# HeatedBed.net
KiCad netlist of a schematic drawn in Altium Designer
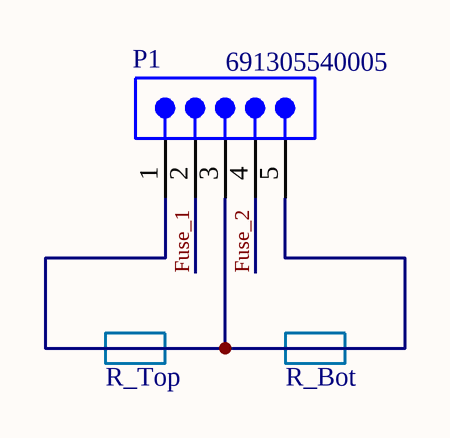
[diagram p0: HeatedBed.SchDoc]

(export (version "E")
  (design (tool "Eeschema 10.0.6"))
  (components
    (comp (ref "P1")
      (value "691305540005")
      (footprint "691305540005")
      (description "691305540005 Terminal Block, R/A Header, 5Pos, Th Rohs Compliant: Yes")
      (libsource (lib "Altium Content Vault") (part "TBL - 1R - 05P - Male"))
    )
  )
  (nets
    (net (code "1") (name "/Fuse_1") (class "Default")
      (node (ref "P1") (pin "2") (pinfunction "2_2") (pintype "passive"))
    )
    (net (code "2") (name "/Fuse_2") (class "Default")
      (node (ref "P1") (pin "4") (pinfunction "4_4") (pintype "passive"))
    )
    (net (code "3") (name "Net-(P1-Pad1)") (class "Default")
      (node (ref "P1") (pin "1") (pinfunction "1_1") (pintype "passive"))
      (node (ref "P1") (pin "3") (pinfunction "3_3") (pintype "passive"))
      (node (ref "P1") (pin "5") (pinfunction "5_5") (pintype "passive"))
    )
  )
)
